# Control_Board_Power.net
KiCad netlist of a schematic drawn in Altium Designer
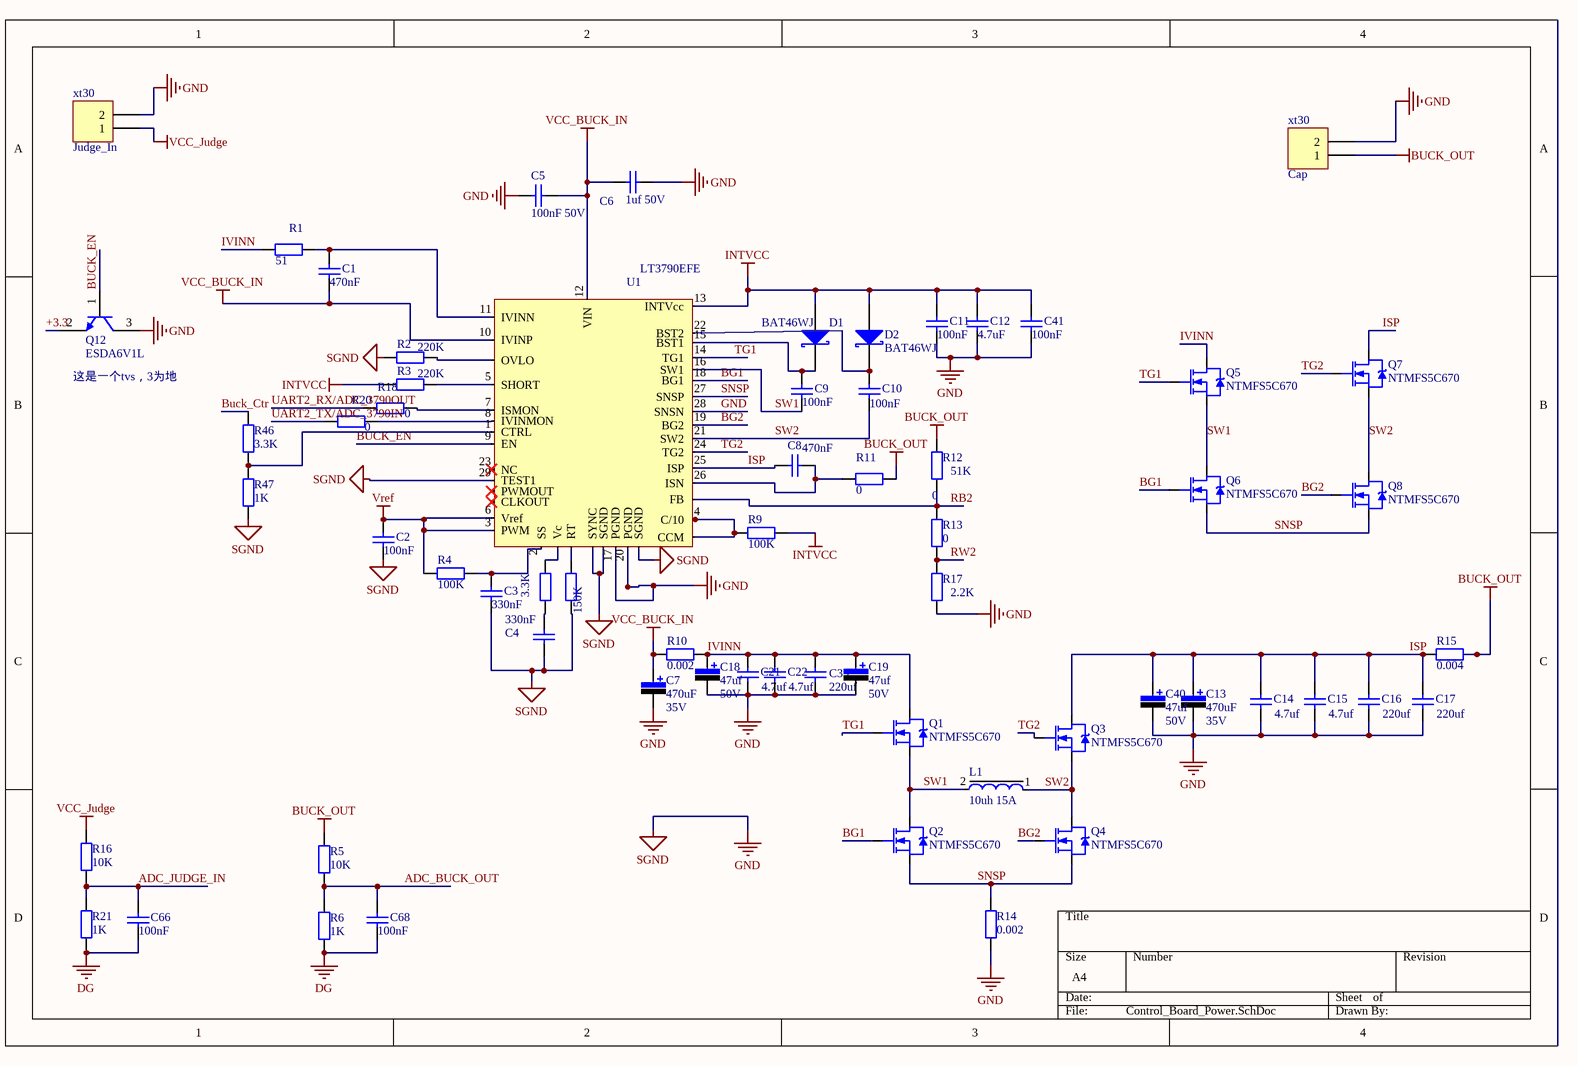
[diagram p0: Control_Board_Power.SchDoc]

(export (version "E")
  (design (tool "Eeschema 10.0.6"))
  (components
    (comp (ref "C1")
      (value "470nF")
      (footprint "r0402")
      (description "无极性电容")
      (fields (field (name "PUBLISHER") "Altium Limited"))
      (libsource (lib "Fszhang") (part "Cap"))
    )
    (comp (ref "C2")
      (value "100nF")
      (footprint "r0402")
      (description "无极性电容")
      (fields (field (name "PUBLISHER") "Altium Limited"))
      (libsource (lib "Fszhang") (part "Cap"))
    )
    (comp (ref "C3")
      (value "330nF")
      (footprint "r0402")
      (description "无极性电容")
      (fields (field (name "PUBLISHER") "Altium Limited"))
      (libsource (lib "Fszhang") (part "Cap"))
    )
    (comp (ref "C4")
      (value "330nF")
      (footprint "r0402")
      (description "无极性电容")
      (fields (field (name "PUBLISHER") "Altium Limited"))
      (libsource (lib "Fszhang") (part "Cap"))
    )
    (comp (ref "C5")
      (value "100nF 50V")
      (footprint "r0402")
      (description "无极性电容")
      (fields (field (name "PUBLISHER") "Altium Limited"))
      (libsource (lib "Fszhang") (part "Cap"))
    )
    (comp (ref "C6")
      (value "1uf 50V")
      (footprint "0805-2")
      (description "无极性电容")
      (fields (field (name "PUBLISHER") "Altium Limited"))
      (libsource (lib "Fszhang") (part "Cap"))
    )
    (comp (ref "C7")
      (value "470uF")
      (footprint "C10X10")
      (description "极性电解电容")
      (fields (field (name "VOL") "35V") (field (name "PUBLISHER") "Altium Limited"))
      (libsource (lib "Fszhang") (part "Cap Pol"))
    )
    (comp (ref "C8")
      (value "470nF")
      (footprint "r0402")
      (description "无极性电容")
      (fields (field (name "Comment") "Cap") (field (name "PUBLISHER") "Altium Limited"))
      (libsource (lib "Fszhang") (part "Cap"))
    )
    (comp (ref "C9")
      (value "100nF")
      (footprint "r0402")
      (description "无极性电容")
      (fields (field (name "PUBLISHER") "Altium Limited"))
      (libsource (lib "Fszhang") (part "Cap"))
    )
    (comp (ref "C10")
      (value "100nF")
      (footprint "r0402")
      (description "无极性电容")
      (fields (field (name "PUBLISHER") "Altium Limited"))
      (libsource (lib "Fszhang") (part "Cap"))
    )
    (comp (ref "C11")
      (value "100nF")
      (footprint "r0402")
      (description "无极性电容")
      (fields (field (name "PUBLISHER") "Altium Limited"))
      (libsource (lib "Fszhang") (part "Cap"))
    )
    (comp (ref "C12")
      (value "4.7uF")
      (footprint "r0402")
      (description "无极性电容")
      (fields (field (name "PUBLISHER") "Altium Limited"))
      (libsource (lib "Fszhang") (part "Cap"))
    )
    (comp (ref "C13")
      (value "470uF")
      (footprint "C10X10")
      (description "极性电解电容")
      (fields
        (field (name "VOL") "35V")
        (field (name "Comment") "Cap Pol")
        (field (name "PUBLISHER") "Altium Limited")
      )
      (libsource (lib "Fszhang") (part "Cap Pol"))
    )
    (comp (ref "C14")
      (value "4.7uf")
      (footprint "1210")
      (description "无极性电容")
      (fields (field (name "PUBLISHER") "Altium Limited"))
      (libsource (lib "Fszhang") (part "Cap"))
    )
    (comp (ref "C15")
      (value "4.7uf")
      (footprint "1210")
      (description "无极性电容")
      (fields (field (name "PUBLISHER") "Altium Limited"))
      (libsource (lib "Fszhang") (part "Cap"))
    )
    (comp (ref "C16")
      (value "220uf")
      (footprint "1210")
      (description "无极性电容")
      (fields (field (name "PUBLISHER") "Altium Limited"))
      (libsource (lib "Fszhang") (part "Cap"))
    )
    (comp (ref "C17")
      (value "220uf")
      (footprint "1210")
      (description "无极性电容")
      (fields (field (name "PUBLISHER") "Altium Limited"))
      (libsource (lib "Fszhang") (part "Cap"))
    )
    (comp (ref "C18")
      (value "47uf")
      (footprint "6.3*7.7MM")
      (description "极性电解电容")
      (fields (field (name "VOL") "50V") (field (name "PUBLISHER") "Altium Limited"))
      (libsource (lib "Fszhang") (part "Cap Pol"))
    )
    (comp (ref "C19")
      (value "47uf")
      (footprint "6.3*7.7MM")
      (description "极性电解电容")
      (fields (field (name "VOL") "50V") (field (name "PUBLISHER") "Altium Limited"))
      (libsource (lib "Fszhang") (part "Cap Pol"))
    )
    (comp (ref "C21")
      (value "4.7uf")
      (footprint "1210")
      (description "无极性电容")
      (fields (field (name "PUBLISHER") "Altium Limited"))
      (libsource (lib "Fszhang") (part "Cap"))
    )
    (comp (ref "C22")
      (value "4.7uf")
      (footprint "1210")
      (description "无极性电容")
      (fields (field (name "PUBLISHER") "Altium Limited"))
      (libsource (lib "Fszhang") (part "Cap"))
    )
    (comp (ref "C39")
      (value "220uf")
      (footprint "1210")
      (description "无极性电容")
      (fields (field (name "PUBLISHER") "Altium Limited"))
      (libsource (lib "Fszhang") (part "Cap"))
    )
    (comp (ref "C40")
      (value "47uf")
      (footprint "6.3*7.7MM")
      (description "极性电解电容")
      (fields
        (field (name "VOL") "50V")
        (field (name "Comment") "Cap Pol")
        (field (name "PUBLISHER") "Altium Limited")
      )
      (libsource (lib "Fszhang") (part "Cap Pol"))
    )
    (comp (ref "C41")
      (value "100nF")
      (footprint "r0402")
      (description "无极性电容")
      (fields (field (name "PUBLISHER") "Altium Limited"))
      (libsource (lib "Fszhang") (part "Cap"))
    )
    (comp (ref "C66")
      (value "100nF")
      (footprint "r0402")
      (description "无极性电容")
      (fields (field (name "PUBLISHER") "Altium Limited"))
      (libsource (lib "Fszhang") (part "Cap"))
    )
    (comp (ref "C68")
      (value "100nF")
      (footprint "r0402")
      (description "无极性电容")
      (fields (field (name "PUBLISHER") "Altium Limited"))
      (libsource (lib "Fszhang") (part "Cap"))
    )
    (comp (ref "Cap")
      (value "xt30")
      (footprint "XT30-M")
      (description "接插件")
      (fields (field (name "PUBLISHER") "Altium Limited"))
      (libsource (lib "Fszhang") (part "Header 2"))
    )
    (comp (ref "D1")
      (value "D-Schottky")
      (footprint "sod323")
      (description "肖特基二极管")
      (fields (field (name "TYPE") "BAT46WJ") (field (name "PUBLISHER") "Altium Limited"))
      (libsource (lib "Fszhang") (part "D-Schottky"))
    )
    (comp (ref "D2")
      (value "D-Schottky")
      (footprint "sod323")
      (description "肖特基二极管")
      (fields (field (name "TYPE") "BAT46WJ") (field (name "PUBLISHER") "Altium Limited"))
      (libsource (lib "Fszhang") (part "D-Schottky"))
    )
    (comp (ref "Judge_In")
      (value "xt30")
      (footprint "XT30-M")
      (description "接插件")
      (fields (field (name "PUBLISHER") "Altium Limited"))
      (libsource (lib "Fszhang") (part "Header 2"))
    )
    (comp (ref "L1")
      (value "10uH")
      (footprint "SER_2000")
      (description "扁铜线功率电感")
      (fields (field (name "L") "10uh 15A"))
      (libsource (lib "super_cap") (part "L"))
    )
    (comp (ref "Q1")
      (value "NTMFS5C670")
      (footprint "pg-tdson-8")
      (description "MOS")
      (fields (field (name "PUBLISHER") "Altium Limited"))
      (libsource (lib "super_cap") (part "NMOS-2"))
    )
    (comp (ref "Q2")
      (value "NTMFS5C670")
      (footprint "pg-tdson-8")
      (description "MOS")
      (fields (field (name "PUBLISHER") "Altium Limited"))
      (libsource (lib "super_cap") (part "NMOS-2"))
    )
    (comp (ref "Q3")
      (value "NTMFS5C670")
      (footprint "pg-tdson-8")
      (description "MOS")
      (fields (field (name "PUBLISHER") "Altium Limited"))
      (libsource (lib "super_cap") (part "NMOS-2"))
    )
    (comp (ref "Q4")
      (value "NTMFS5C670")
      (footprint "pg-tdson-8")
      (description "MOS")
      (fields (field (name "PUBLISHER") "Altium Limited"))
      (libsource (lib "super_cap") (part "NMOS-2"))
    )
    (comp (ref "Q5")
      (value "NTMFS5C670")
      (footprint "pg-tdson-8")
      (description "MOS")
      (fields (field (name "PUBLISHER") "Altium Limited"))
      (libsource (lib "super_cap") (part "NMOS-2"))
    )
    (comp (ref "Q6")
      (value "NTMFS5C670")
      (footprint "pg-tdson-8")
      (description "MOS")
      (fields (field (name "PUBLISHER") "Altium Limited"))
      (libsource (lib "super_cap") (part "NMOS-2"))
    )
    (comp (ref "Q7")
      (value "NTMFS5C670")
      (footprint "pg-tdson-8")
      (description "MOS")
      (fields (field (name "PUBLISHER") "Altium Limited"))
      (libsource (lib "super_cap") (part "NMOS-2"))
    )
    (comp (ref "Q8")
      (value "NTMFS5C670")
      (footprint "pg-tdson-8")
      (description "MOS")
      (fields (field (name "PUBLISHER") "Altium Limited"))
      (libsource (lib "super_cap") (part "NMOS-2"))
    )
    (comp (ref "Q12")
      (value "ESDA6V1L")
      (footprint "SOT-23")
      (description "TVS(l懒得找原理图了)")
      (fields (field (name "PUBLISHER") "Altium Limited"))
      (libsource (lib "fszhang") (part "SS8050"))
    )
    (comp (ref "R1")
      (value "51")
      (footprint "r0402")
      (description "贴片电阻")
      (fields (field (name "PUBLISHER") "Altium Limited"))
      (libsource (lib "") (part "Res1_1"))
    )
    (comp (ref "R2")
      (value "220K")
      (footprint "r0402")
      (description "贴片电阻")
      (fields (field (name "PUBLISHER") "Altium Limited"))
      (libsource (lib "") (part "Res1_1"))
    )
    (comp (ref "R3")
      (value "220K")
      (footprint "r0402")
      (description "贴片电阻")
      (fields (field (name "PUBLISHER") "Altium Limited"))
      (libsource (lib "") (part "Res1_1"))
    )
    (comp (ref "R4")
      (value "100K")
      (footprint "r0402")
      (description "贴片电阻")
      (fields (field (name "PUBLISHER") "Altium Limited"))
      (libsource (lib "") (part "Res1_1"))
    )
    (comp (ref "R5")
      (value "10K")
      (footprint "r0402")
      (description "贴片电阻")
      (fields (field (name "PUBLISHER") "Altium Limited"))
      (libsource (lib "") (part "Res1_2"))
    )
    (comp (ref "R6")
      (value "1K")
      (footprint "r0402")
      (description "贴片电阻")
      (fields (field (name "PUBLISHER") "Altium Limited"))
      (libsource (lib "Fszhang") (part "Res1"))
    )
    (comp (ref "R7")
      (value "3.3K")
      (footprint "r0402")
      (description "贴片电阻")
      (fields (field (name "PUBLISHER") "Altium Limited"))
      (libsource (lib "") (part "Res1_2"))
    )
    (comp (ref "R8")
      (value "150K")
      (footprint "r0402")
      (description "贴片电阻")
      (fields (field (name "PUBLISHER") "Altium Limited"))
      (libsource (lib "") (part "Res1_2"))
    )
    (comp (ref "R9")
      (value "100K")
      (footprint "r0402")
      (description "贴片电阻")
      (fields (field (name "PUBLISHER") "Altium Limited"))
      (libsource (lib "") (part "Res1_1"))
    )
    (comp (ref "R10")
      (value "0.002")
      (footprint "2512")
      (description "贴片电阻")
      (fields (field (name "PUBLISHER") "Altium Limited"))
      (libsource (lib "") (part "Res1_1"))
    )
    (comp (ref "R11")
      (value "0")
      (footprint "r0402")
      (description "贴片电阻")
      (fields (field (name "PUBLISHER") "Altium Limited"))
      (libsource (lib "") (part "Res1_1"))
    )
    (comp (ref "R12")
      (value "51K")
      (footprint "r0402")
      (description "贴片电阻")
      (fields (field (name "PUBLISHER") "Altium Limited"))
      (libsource (lib "") (part "Res1_2"))
    )
    (comp (ref "R13")
      (value "0")
      (footprint "r0402")
      (description "贴片电阻")
      (fields (field (name "ALTIUM_VALUE") "0") (field (name "PUBLISHER") "Altium Limited"))
      (libsource (lib "Fszhang") (part "Res1"))
    )
    (comp (ref "R14")
      (value "0.002")
      (footprint "2512")
      (description "贴片电阻")
      (fields (field (name "PUBLISHER") "Altium Limited"))
      (libsource (lib "Fszhang") (part "Res1"))
    )
    (comp (ref "R15")
      (value "0.004")
      (footprint "2512")
      (description "贴片电阻")
      (fields (field (name "PUBLISHER") "Altium Limited"))
      (libsource (lib "") (part "Res1_1"))
    )
    (comp (ref "R16")
      (value "10K")
      (footprint "r0402")
      (description "贴片电阻")
      (fields (field (name "PUBLISHER") "Altium Limited"))
      (libsource (lib "") (part "Res1_2"))
    )
    (comp (ref "R17")
      (value "2.2K")
      (footprint "r0402")
      (description "贴片电阻")
      (fields (field (name "PUBLISHER") "Altium Limited"))
      (libsource (lib "") (part "Res1_2"))
    )
    (comp (ref "R18")
      (value "0")
      (footprint "R0402")
      (description "贴片电阻")
      (fields (field (name "Comment") "51") (field (name "PUBLISHER") "Altium Limited"))
      (libsource (lib "") (part "Res1_1"))
    )
    (comp (ref "R20")
      (value "0")
      (footprint "r0402")
      (description "贴片电阻")
      (fields (field (name "Comment") "51") (field (name "PUBLISHER") "Altium Limited"))
      (libsource (lib "") (part "Res1_1"))
    )
    (comp (ref "R21")
      (value "1K")
      (footprint "r0402")
      (description "贴片电阻")
      (fields (field (name "PUBLISHER") "Altium Limited"))
      (libsource (lib "Fszhang") (part "Res1"))
    )
    (comp (ref "R46")
      (value "3.3K")
      (footprint "r0402")
      (description "贴片电阻")
      (fields (field (name "PUBLISHER") "Altium Limited"))
      (libsource (lib "") (part "Res1_2"))
    )
    (comp (ref "R47")
      (value "1K")
      (footprint "r0402")
      (description "贴片电阻")
      (fields (field (name "PUBLISHER") "Altium Limited"))
      (libsource (lib "") (part "Res1_2"))
    )
    (comp (ref "U1")
      (value "LT3790EFE")
      (footprint "TSSOP38")
      (description "DC-DC芯片")
      (libsource (lib "super_cap") (part "LT3790"))
    )
  )
  (nets
    (net (code "1") (name "/+3.3") (class "Default")
      (node (ref "Q12") (pin "2") (pinfunction "E_2") (pintype "passive"))
    )
    (net (code "2") (name "/ADC_BUCK_OUT") (class "Default")
      (node (ref "C68") (pin "2") (pinfunction "2_2") (pintype "passive"))
      (node (ref "R5") (pin "1") (pinfunction "1_1") (pintype "passive"))
      (node (ref "R6") (pin "1") (pinfunction "1_1") (pintype "passive"))
    )
    (net (code "3") (name "/ADC_JUDGE_IN") (class "Default")
      (node (ref "C66") (pin "2") (pinfunction "2_2") (pintype "passive"))
      (node (ref "R16") (pin "1") (pinfunction "1_1") (pintype "passive"))
      (node (ref "R21") (pin "1") (pinfunction "1_1") (pintype "passive"))
    )
    (net (code "4") (name "/BG1") (class "Default")
      (node (ref "Q2") (pin "1") (pinfunction "G_1") (pintype "passive"))
      (node (ref "Q6") (pin "1") (pinfunction "G_1") (pintype "passive"))
      (node (ref "U1") (pin "18") (pinfunction "BG1_18") (pintype "passive"))
    )
    (net (code "5") (name "/BG2") (class "Default")
      (node (ref "Q4") (pin "1") (pinfunction "G_1") (pintype "passive"))
      (node (ref "Q8") (pin "1") (pinfunction "G_1") (pintype "passive"))
      (node (ref "U1") (pin "19") (pinfunction "BG2_19") (pintype "passive"))
    )
    (net (code "6") (name "/BUCK_EN") (class "Default")
      (node (ref "Q12") (pin "1") (pinfunction "B_1") (pintype "passive"))
      (node (ref "U1") (pin "9") (pinfunction "EN_9") (pintype "passive"))
    )
    (net (code "7") (name "/Buck_Ctr") (class "Default")
      (node (ref "R46") (pin "2") (pinfunction "2_2") (pintype "passive"))
    )
    (net (code "8") (name "/ISP") (class "Default")
      (node (ref "C13") (pin "1") (pinfunction "1_1") (pintype "passive"))
      (node (ref "C14") (pin "2") (pinfunction "2_2") (pintype "passive"))
      (node (ref "C15") (pin "2") (pinfunction "2_2") (pintype "passive"))
      (node (ref "C16") (pin "2") (pinfunction "2_2") (pintype "passive"))
      (node (ref "C17") (pin "2") (pinfunction "2_2") (pintype "passive"))
      (node (ref "C40") (pin "1") (pinfunction "1_1") (pintype "passive"))
      (node (ref "C8") (pin "2") (pinfunction "2_2") (pintype "passive"))
      (node (ref "Q3") (pin "2") (pinfunction "D_2") (pintype "passive"))
      (node (ref "Q7") (pin "2") (pinfunction "D_2") (pintype "passive"))
      (node (ref "R15") (pin "1") (pinfunction "1_1") (pintype "passive"))
      (node (ref "U1") (pin "25") (pinfunction "ISP_25") (pintype "passive"))
    )
    (net (code "9") (name "/IVINN") (class "Default")
      (node (ref "C18") (pin "1") (pinfunction "1_1") (pintype "passive"))
      (node (ref "C19") (pin "1") (pinfunction "1_1") (pintype "passive"))
      (node (ref "C21") (pin "2") (pinfunction "2_2") (pintype "passive"))
      (node (ref "C22") (pin "2") (pinfunction "2_2") (pintype "passive"))
      (node (ref "C39") (pin "2") (pinfunction "2_2") (pintype "passive"))
      (node (ref "Q1") (pin "2") (pinfunction "D_2") (pintype "passive"))
      (node (ref "Q5") (pin "2") (pinfunction "D_2") (pintype "passive"))
      (node (ref "R1") (pin "1") (pinfunction "1_1") (pintype "passive"))
      (node (ref "R10") (pin "2") (pinfunction "2_2") (pintype "passive"))
    )
    (net (code "10") (name "/RB2") (class "Default")
      (node (ref "R12") (pin "1") (pinfunction "1_1") (pintype "passive"))
      (node (ref "R13") (pin "1") (pinfunction "1_1") (pintype "passive"))
      (node (ref "U1") (pin "37") (pinfunction "FB_37") (pintype "passive"))
    )
    (net (code "11") (name "/RW2") (class "Default")
      (node (ref "R13") (pin "2") (pinfunction "2_2") (pintype "passive"))
      (node (ref "R17") (pin "2") (pinfunction "2_2") (pintype "passive"))
    )
    (net (code "12") (name "/SNSP") (class "Default")
      (node (ref "Q2") (pin "3") (pinfunction "S_3") (pintype "passive"))
      (node (ref "Q4") (pin "3") (pinfunction "S_3") (pintype "passive"))
      (node (ref "Q6") (pin "3") (pinfunction "S_3") (pintype "passive"))
      (node (ref "Q8") (pin "3") (pinfunction "S_3") (pintype "passive"))
      (node (ref "R14") (pin "1") (pinfunction "1_1") (pintype "passive"))
      (node (ref "U1") (pin "27") (pinfunction "SNSP_27") (pintype "passive"))
    )
    (net (code "13") (name "/SW1") (class "Default")
      (node (ref "C9") (pin "1") (pinfunction "1_1") (pintype "passive"))
      (node (ref "L1") (pin "2") (pinfunction "1_2") (pintype "passive"))
      (node (ref "Q1") (pin "3") (pinfunction "S_3") (pintype "passive"))
      (node (ref "Q2") (pin "2") (pinfunction "D_2") (pintype "passive"))
      (node (ref "Q5") (pin "3") (pinfunction "S_3") (pintype "passive"))
      (node (ref "Q6") (pin "2") (pinfunction "D_2") (pintype "passive"))
      (node (ref "U1") (pin "16") (pinfunction "SW1_16") (pintype "passive"))
    )
    (net (code "14") (name "/SW2") (class "Default")
      (node (ref "C10") (pin "1") (pinfunction "1_1") (pintype "passive"))
      (node (ref "L1") (pin "1") (pinfunction "2_1") (pintype "passive"))
      (node (ref "Q3") (pin "3") (pinfunction "S_3") (pintype "passive"))
      (node (ref "Q4") (pin "2") (pinfunction "D_2") (pintype "passive"))
      (node (ref "Q7") (pin "3") (pinfunction "S_3") (pintype "passive"))
      (node (ref "Q8") (pin "2") (pinfunction "D_2") (pintype "passive"))
      (node (ref "U1") (pin "21") (pinfunction "SW2_21") (pintype "passive"))
    )
    (net (code "15") (name "/TG1") (class "Default")
      (node (ref "Q1") (pin "1") (pinfunction "G_1") (pintype "passive"))
      (node (ref "Q5") (pin "1") (pinfunction "G_1") (pintype "passive"))
      (node (ref "U1") (pin "14") (pinfunction "TG1_14") (pintype "passive"))
    )
    (net (code "16") (name "/TG2") (class "Default")
      (node (ref "Q3") (pin "1") (pinfunction "G_1") (pintype "passive"))
      (node (ref "Q7") (pin "1") (pinfunction "G_1") (pintype "passive"))
      (node (ref "U1") (pin "24") (pinfunction "TG2_24") (pintype "passive"))
    )
    (net (code "17") (name "/UART2_RX{slash}ADC_3790OUT") (class "Default")
      (node (ref "R18") (pin "1") (pinfunction "1_1") (pintype "passive"))
    )
    (net (code "18") (name "/UART2_TX{slash}ADC_3790IN") (class "Default")
      (node (ref "R20") (pin "1") (pinfunction "1_1") (pintype "passive"))
    )
    (net (code "19") (name "BUCK_OUT") (class "Default")
      (node (ref "Cap") (pin "1") (pinfunction "1_1") (pintype "passive"))
      (node (ref "R11") (pin "2") (pinfunction "2_2") (pintype "passive"))
      (node (ref "R12") (pin "2") (pinfunction "2_2") (pintype "passive"))
      (node (ref "R15") (pin "2") (pinfunction "2_2") (pintype "passive"))
      (node (ref "R5") (pin "2") (pinfunction "2_2") (pintype "passive"))
    )
    (net (code "20") (name "DG") (class "Default")
      (node (ref "C66") (pin "1") (pinfunction "1_1") (pintype "passive"))
      (node (ref "C68") (pin "1") (pinfunction "1_1") (pintype "passive"))
      (node (ref "R21") (pin "2") (pinfunction "2_2") (pintype "passive"))
      (node (ref "R6") (pin "2") (pinfunction "2_2") (pintype "passive"))
    )
    (net (code "21") (name "GND") (class "Default")
      (node (ref "C11") (pin "1") (pinfunction "1_1") (pintype "passive"))
      (node (ref "C12") (pin "1") (pinfunction "1_1") (pintype "passive"))
      (node (ref "C13") (pin "2") (pinfunction "2_2") (pintype "passive"))
      (node (ref "C14") (pin "1") (pinfunction "1_1") (pintype "passive"))
      (node (ref "C15") (pin "1") (pinfunction "1_1") (pintype "passive"))
      (node (ref "C16") (pin "1") (pinfunction "1_1") (pintype "passive"))
      (node (ref "C17") (pin "1") (pinfunction "1_1") (pintype "passive"))
      (node (ref "C18") (pin "2") (pinfunction "2_2") (pintype "passive"))
      (node (ref "C19") (pin "2") (pinfunction "2_2") (pintype "passive"))
      (node (ref "C2") (pin "1") (pinfunction "1_1") (pintype "passive"))
      (node (ref "C21") (pin "1") (pinfunction "1_1") (pintype "passive"))
      (node (ref "C22") (pin "1") (pinfunction "1_1") (pintype "passive"))
      (node (ref "C3") (pin "1") (pinfunction "1_1") (pintype "passive"))
      (node (ref "C39") (pin "1") (pinfunction "1_1") (pintype "passive"))
      (node (ref "C4") (pin "1") (pinfunction "1_1") (pintype "passive"))
      (node (ref "C40") (pin "2") (pinfunction "2_2") (pintype "passive"))
      (node (ref "C41") (pin "1") (pinfunction "1_1") (pintype "passive"))
      (node (ref "C5") (pin "1") (pinfunction "1_1") (pintype "passive"))
      (node (ref "C6") (pin "1") (pinfunction "1_1") (pintype "passive"))
      (node (ref "C7") (pin "2") (pinfunction "2_2") (pintype "passive"))
      (node (ref "Cap") (pin "2") (pinfunction "2_2") (pintype "passive"))
      (node (ref "Judge_In") (pin "2") (pinfunction "2_2") (pintype "passive"))
      (node (ref "Q12") (pin "3") (pinfunction "C_3") (pintype "passive"))
      (node (ref "R14") (pin "2") (pinfunction "2_2") (pintype "passive"))
      (node (ref "R17") (pin "1") (pinfunction "1_1") (pintype "passive"))
      (node (ref "R2") (pin "1") (pinfunction "1_1") (pintype "passive"))
      (node (ref "R47") (pin "1") (pinfunction "1_1") (pintype "passive"))
      (node (ref "R8") (pin "1") (pinfunction "1_1") (pintype "passive"))
      (node (ref "U1") (pin "17") (pinfunction "PGND_17") (pintype "passive"))
      (node (ref "U1") (pin "20") (pinfunction "PGND_20") (pintype "passive"))
      (node (ref "U1") (pin "28") (pinfunction "SNSN_28") (pintype "passive"))
      (node (ref "U1") (pin "29") (pinfunction "TEST1_29") (pintype "passive"))
      (node (ref "U1") (pin "30") (pinfunction "SGND_30") (pintype "passive"))
      (node (ref "U1") (pin "34") (pinfunction "SYNC_34") (pintype "passive"))
      (node (ref "U1") (pin "39") (pinfunction "SGND_39") (pintype "passive"))
    )
    (net (code "22") (name "INTVCC") (class "Default")
      (node (ref "C11") (pin "2") (pinfunction "2_2") (pintype "passive"))
      (node (ref "C12") (pin "2") (pinfunction "2_2") (pintype "passive"))
      (node (ref "C41") (pin "2") (pinfunction "2_2") (pintype "passive"))
      (node (ref "D1") (pin "1") (pinfunction "A_1") (pintype "passive"))
      (node (ref "D2") (pin "1") (pinfunction "A_1") (pintype "passive"))
      (node (ref "R3") (pin "1") (pinfunction "1_1") (pintype "passive"))
      (node (ref "R9") (pin "2") (pinfunction "2_2") (pintype "passive"))
      (node (ref "U1") (pin "13") (pinfunction "INTVcc_13") (pintype "passive"))
    )
    (net (code "23") (name "Net-(C4-Pad2)") (class "Default")
      (node (ref "C4") (pin "2") (pinfunction "2_2") (pintype "passive"))
      (node (ref "R7") (pin "1") (pinfunction "1_1") (pintype "passive"))
    )
    (net (code "24") (name "Net-(D1-K)") (class "Default")
      (node (ref "C9") (pin "2") (pinfunction "2_2") (pintype "passive"))
      (node (ref "D1") (pin "2") (pinfunction "K_2") (pintype "passive"))
      (node (ref "U1") (pin "15") (pinfunction "BST1_15") (pintype "passive"))
    )
    (net (code "25") (name "Net-(D2-K)") (class "Default")
      (node (ref "C10") (pin "2") (pinfunction "2_2") (pintype "passive"))
      (node (ref "D2") (pin "2") (pinfunction "K_2") (pintype "passive"))
      (node (ref "U1") (pin "22") (pinfunction "BST2_22") (pintype "passive"))
    )
    (net (code "26") (name "Net-(U1-CCM)") (class "Default")
      (node (ref "R9") (pin "1") (pinfunction "1_1") (pintype "passive"))
      (node (ref "U1") (pin "32") (pinfunction "CCM_32") (pintype "passive"))
      (node (ref "U1") (pin "4") (pinfunction "C/10_4") (pintype "passive"))
    )
    (net (code "27") (name "Net-(U1-CTRL)") (class "Default")
      (node (ref "R46") (pin "1") (pinfunction "1_1") (pintype "passive"))
      (node (ref "R47") (pin "2") (pinfunction "2_2") (pintype "passive"))
      (node (ref "U1") (pin "1") (pinfunction "CTRL_1") (pintype "passive"))
    )
    (net (code "28") (name "Net-(U1-ISMON)") (class "Default")
      (node (ref "R18") (pin "2") (pinfunction "2_2") (pintype "passive"))
      (node (ref "U1") (pin "7") (pinfunction "ISMON_7") (pintype "passive"))
    )
    (net (code "29") (name "Net-(U1-ISN)") (class "Default")
      (node (ref "C8") (pin "1") (pinfunction "1_1") (pintype "passive"))
      (node (ref "R11") (pin "1") (pinfunction "1_1") (pintype "passive"))
      (node (ref "U1") (pin "26") (pinfunction "ISN_26") (pintype "passive"))
    )
    (net (code "30") (name "Net-(U1-IVINMON)") (class "Default")
      (node (ref "R20") (pin "2") (pinfunction "2_2") (pintype "passive"))
      (node (ref "U1") (pin "8") (pinfunction "IVINMON_8") (pintype "passive"))
    )
    (net (code "31") (name "Net-(U1-IVINN)") (class "Default")
      (node (ref "C1") (pin "2") (pinfunction "2_2") (pintype "passive"))
      (node (ref "R1") (pin "2") (pinfunction "2_2") (pintype "passive"))
      (node (ref "U1") (pin "11") (pinfunction "IVINN_11") (pintype "passive"))
    )
    (net (code "32") (name "Net-(U1-OVLO)") (class "Default")
      (node (ref "R2") (pin "2") (pinfunction "2_2") (pintype "passive"))
      (node (ref "U1") (pin "38") (pinfunction "OVLO_38") (pintype "passive"))
    )
    (net (code "33") (name "Net-(U1-RT)") (class "Default")
      (node (ref "R8") (pin "2") (pinfunction "2_2") (pintype "passive"))
      (node (ref "U1") (pin "35") (pinfunction "RT_35") (pintype "passive"))
    )
    (net (code "34") (name "Net-(U1-SHORT)") (class "Default")
      (node (ref "R3") (pin "2") (pinfunction "2_2") (pintype "passive"))
      (node (ref "U1") (pin "5") (pinfunction "SHORT_5") (pintype "passive"))
    )
    (net (code "35") (name "Net-(U1-SS)") (class "Default")
      (node (ref "C3") (pin "2") (pinfunction "2_2") (pintype "passive"))
      (node (ref "R4") (pin "2") (pinfunction "2_2") (pintype "passive"))
      (node (ref "U1") (pin "2") (pinfunction "SS_2") (pintype "passive"))
    )
    (net (code "36") (name "Net-(U1-Vc)") (class "Default")
      (node (ref "R7") (pin "2") (pinfunction "2_2") (pintype "passive"))
      (node (ref "U1") (pin "36") (pinfunction "Vc_36") (pintype "passive"))
    )
    (net (code "37") (name "VCC_BUCK_IN") (class "Default")
      (node (ref "C1") (pin "1") (pinfunction "1_1") (pintype "passive"))
      (node (ref "C5") (pin "2") (pinfunction "2_2") (pintype "passive"))
      (node (ref "C6") (pin "2") (pinfunction "2_2") (pintype "passive"))
      (node (ref "C7") (pin "1") (pinfunction "1_1") (pintype "passive"))
      (node (ref "R10") (pin "1") (pinfunction "1_1") (pintype "passive"))
      (node (ref "U1") (pin "10") (pinfunction "IVINP_10") (pintype "passive"))
      (node (ref "U1") (pin "12") (pinfunction "VIN_12") (pintype "passive"))
    )
    (net (code "38") (name "VCC_Judge") (class "Default")
      (node (ref "Judge_In") (pin "1") (pinfunction "1_1") (pintype "passive"))
      (node (ref "R16") (pin "2") (pinfunction "2_2") (pintype "passive"))
    )
    (net (code "39") (name "Vref") (class "Default")
      (node (ref "C2") (pin "2") (pinfunction "2_2") (pintype "passive"))
      (node (ref "R4") (pin "1") (pinfunction "1_1") (pintype "passive"))
      (node (ref "U1") (pin "3") (pinfunction "PWM_3") (pintype "passive"))
      (node (ref "U1") (pin "6") (pinfunction "Vref_6") (pintype "passive"))
    )
    (net (code "40") (name "unconnected-(U1-CLKOUT-Pad33)") (class "Default")
      (node (ref "U1") (pin "33") (pinfunction "CLKOUT_33") (pintype "passive+no_connect"))
    )
    (net (code "41") (name "unconnected-(U1-NC-Pad23)") (class "Default")
      (node (ref "U1") (pin "23") (pinfunction "NC_23") (pintype "passive+no_connect"))
    )
    (net (code "42") (name "unconnected-(U1-PWMOUT-Pad31)") (class "Default")
      (node (ref "U1") (pin "31") (pinfunction "PWMOUT_31") (pintype "passive+no_connect"))
    )
  )
)
